# Sheet1.net
KiCad netlist of a schematic drawn in Altium Designer
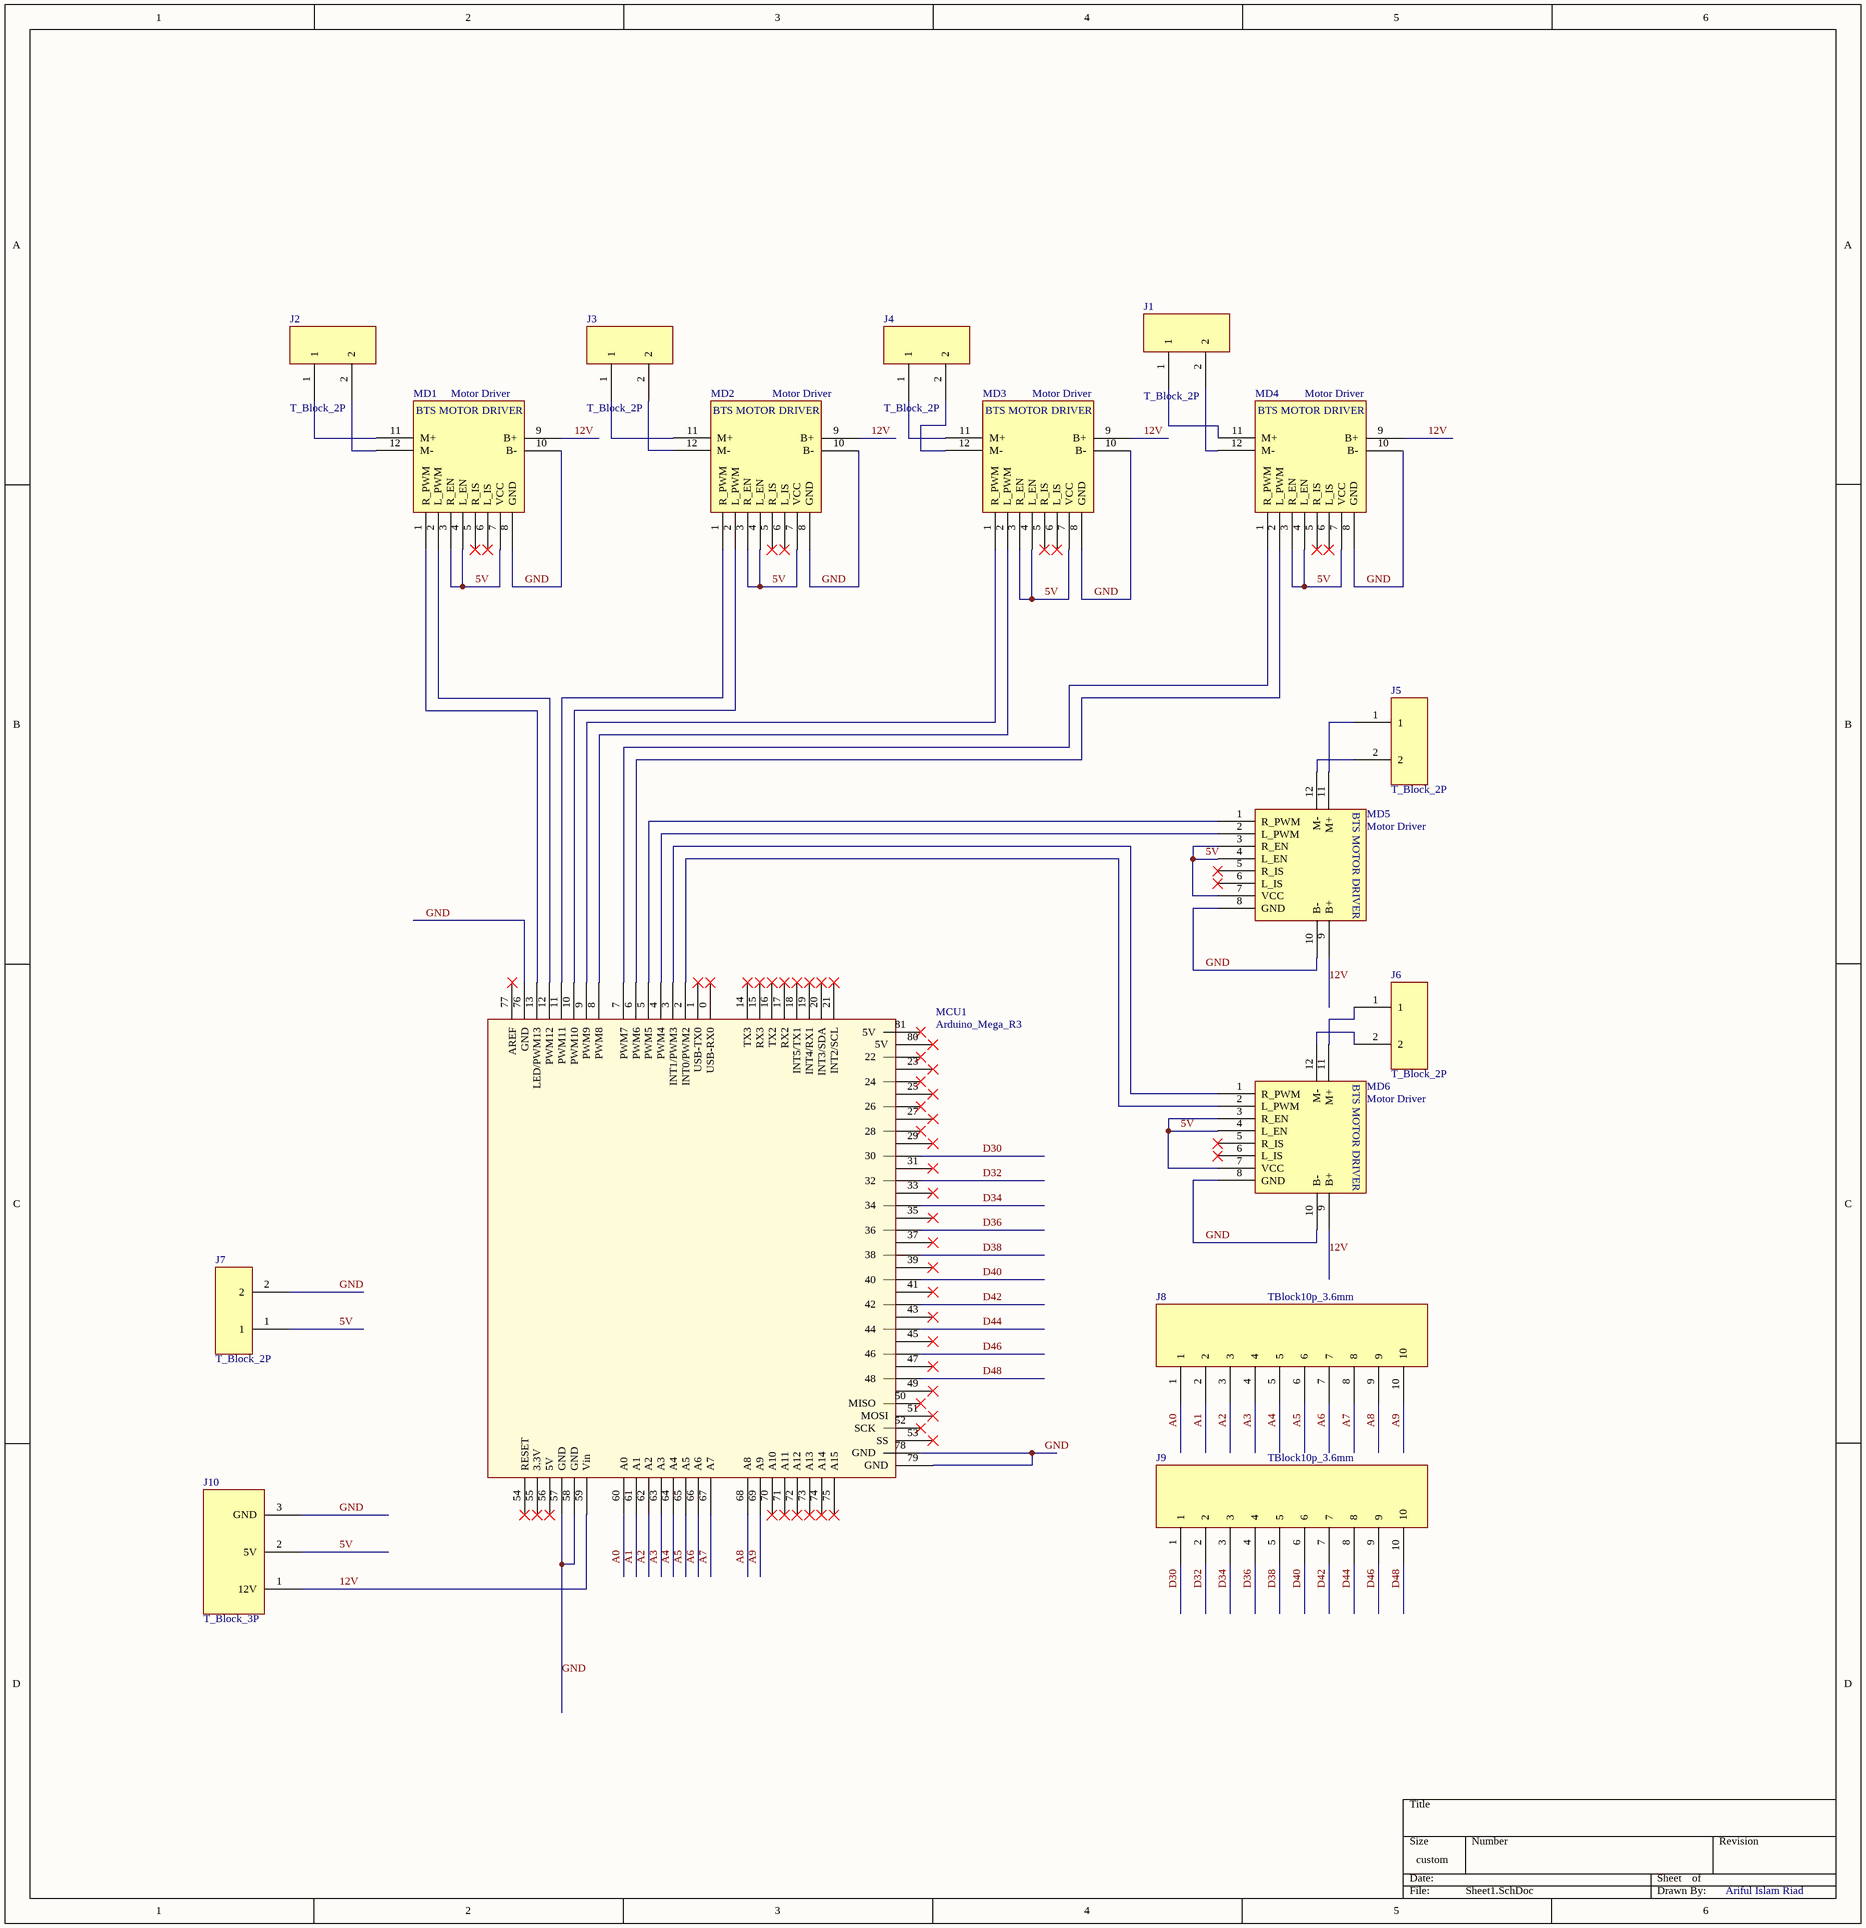
[diagram p0: Sheet1.SchDoc]

(export (version "E")
  (design (tool "Eeschema 10.0.6"))
  (components
    (comp (ref "J1")
      (value "T_Block_2P")
      (footprint "T_Block_2P")
      (description "Terminal")
      (libsource (lib "Schlib1") (part "T_Block_2P"))
    )
    (comp (ref "J2")
      (value "T_Block_2P")
      (footprint "T_Block_2P")
      (description "Terminal")
      (libsource (lib "Schlib1") (part "T_Block_2P"))
    )
    (comp (ref "J3")
      (value "T_Block_2P")
      (footprint "T_Block_2P")
      (description "Terminal")
      (libsource (lib "Schlib1") (part "T_Block_2P"))
    )
    (comp (ref "J4")
      (value "T_Block_2P")
      (footprint "T_Block_2P")
      (description "Terminal")
      (libsource (lib "Schlib1") (part "T_Block_2P"))
    )
    (comp (ref "J5")
      (value "T_Block_2P")
      (footprint "T_Block_2P")
      (description "Terminal")
      (libsource (lib "") (part "T_Block_2P_1"))
    )
    (comp (ref "J6")
      (value "T_Block_2P")
      (footprint "T_Block_2P")
      (description "Terminal")
      (libsource (lib "") (part "T_Block_2P_1"))
    )
    (comp (ref "J7")
      (value "T_Block_2P")
      (footprint "T_Block_2P")
      (description "Terminal")
      (libsource (lib "") (part "T_Block_2P_2"))
    )
    (comp (ref "J8")
      (value "TBlock10p_3.6mm")
      (footprint "T_block_3.6mm")
      (description "Terminal")
      (libsource (lib "Schlib1") (part "TBlock10p_3.6mm"))
    )
    (comp (ref "J9")
      (value "TBlock10p_3.6mm")
      (footprint "T_block_3.6mm")
      (description "Terminal")
      (libsource (lib "Schlib1") (part "TBlock10p_3.6mm"))
    )
    (comp (ref "J10")
      (value "T_Block_3P")
      (footprint "T_Block_3P")
      (description "Terminal")
      (libsource (lib "Schlib1") (part "T_Block_3P"))
    )
    (comp (ref "MCU1")
      (value "Arduino_Mega_R3")
      (footprint "PCB_footprint_mega")
      (description "Arduino Mega")
      (libsource (lib "Schlib1") (part "Mega"))
    )
    (comp (ref "MD1") (value "Motor Driver") (footprint "PCB_BTS") (libsource (lib "Schlib1") (part "BTS")))
    (comp (ref "MD2") (value "Motor Driver") (footprint "PCB_BTS") (libsource (lib "Schlib1") (part "BTS")))
    (comp (ref "MD3") (value "Motor Driver") (footprint "PCB_BTS") (libsource (lib "Schlib1") (part "BTS")))
    (comp (ref "MD4") (value "Motor Driver") (footprint "PCB_BTS") (libsource (lib "Schlib1") (part "BTS")))
    (comp (ref "MD5") (value "Motor Driver") (footprint "PCB_BTS") (libsource (lib "") (part "BTS_1")))
    (comp (ref "MD6") (value "Motor Driver") (footprint "PCB_BTS") (libsource (lib "") (part "BTS_1")))
  )
  (nets
    (net (code "1") (name "/5V") (class "Default")
      (node (ref "J10") (pin "2") (pinfunction "5V_2") (pintype "passive"))
      (node (ref "J7") (pin "1") (pinfunction "1_1") (pintype "passive"))
      (node (ref "MD1") (pin "3") (pinfunction "R_EN_3") (pintype "passive"))
      (node (ref "MD1") (pin "4") (pinfunction "L_EN_4") (pintype "passive"))
      (node (ref "MD1") (pin "7") (pinfunction "VCC_7") (pintype "passive"))
      (node (ref "MD2") (pin "3") (pinfunction "R_EN_3") (pintype "passive"))
      (node (ref "MD2") (pin "4") (pinfunction "L_EN_4") (pintype "passive"))
      (node (ref "MD2") (pin "7") (pinfunction "VCC_7") (pintype "passive"))
      (node (ref "MD3") (pin "3") (pinfunction "R_EN_3") (pintype "passive"))
      (node (ref "MD3") (pin "4") (pinfunction "L_EN_4") (pintype "passive"))
      (node (ref "MD3") (pin "7") (pinfunction "VCC_7") (pintype "passive"))
      (node (ref "MD4") (pin "3") (pinfunction "R_EN_3") (pintype "passive"))
      (node (ref "MD4") (pin "4") (pinfunction "L_EN_4") (pintype "passive"))
      (node (ref "MD4") (pin "7") (pinfunction "VCC_7") (pintype "passive"))
      (node (ref "MD5") (pin "3") (pinfunction "R_EN_3") (pintype "passive"))
      (node (ref "MD5") (pin "4") (pinfunction "L_EN_4") (pintype "passive"))
      (node (ref "MD5") (pin "7") (pinfunction "VCC_7") (pintype "passive"))
      (node (ref "MD6") (pin "3") (pinfunction "R_EN_3") (pintype "passive"))
      (node (ref "MD6") (pin "4") (pinfunction "L_EN_4") (pintype "passive"))
      (node (ref "MD6") (pin "7") (pinfunction "VCC_7") (pintype "passive"))
    )
    (net (code "2") (name "/12V") (class "Default")
      (node (ref "J10") (pin "1") (pinfunction "12V_1") (pintype "passive"))
      (node (ref "MCU1") (pin "59") (pinfunction "Vin_59") (pintype "passive"))
      (node (ref "MD1") (pin "9") (pinfunction "B+_9") (pintype "passive"))
      (node (ref "MD2") (pin "9") (pinfunction "B+_9") (pintype "passive"))
      (node (ref "MD3") (pin "9") (pinfunction "B+_9") (pintype "passive"))
      (node (ref "MD4") (pin "9") (pinfunction "B+_9") (pintype "passive"))
      (node (ref "MD5") (pin "9") (pinfunction "B+_9") (pintype "passive"))
      (node (ref "MD6") (pin "9") (pinfunction "B+_9") (pintype "passive"))
    )
    (net (code "3") (name "/A0") (class "Default")
      (node (ref "J8") (pin "1") (pinfunction "1_1") (pintype "passive"))
      (node (ref "MCU1") (pin "60") (pinfunction "A0_60") (pintype "passive"))
    )
    (net (code "4") (name "/A1") (class "Default")
      (node (ref "J8") (pin "2") (pinfunction "2_2") (pintype "passive"))
      (node (ref "MCU1") (pin "61") (pinfunction "A1_61") (pintype "passive"))
    )
    (net (code "5") (name "/A2") (class "Default")
      (node (ref "J8") (pin "3") (pinfunction "3_3") (pintype "passive"))
      (node (ref "MCU1") (pin "62") (pinfunction "A2_62") (pintype "passive"))
    )
    (net (code "6") (name "/A3") (class "Default")
      (node (ref "J8") (pin "4") (pinfunction "4_4") (pintype "passive"))
      (node (ref "MCU1") (pin "63") (pinfunction "A3_63") (pintype "passive"))
    )
    (net (code "7") (name "/A4") (class "Default")
      (node (ref "J8") (pin "5") (pinfunction "5_5") (pintype "passive"))
      (node (ref "MCU1") (pin "64") (pinfunction "A4_64") (pintype "passive"))
    )
    (net (code "8") (name "/A5") (class "Default")
      (node (ref "J8") (pin "6") (pinfunction "6_6") (pintype "passive"))
      (node (ref "MCU1") (pin "65") (pinfunction "A5_65") (pintype "passive"))
    )
    (net (code "9") (name "/A6") (class "Default")
      (node (ref "J8") (pin "7") (pinfunction "7_7") (pintype "passive"))
      (node (ref "MCU1") (pin "66") (pinfunction "A6_66") (pintype "passive"))
    )
    (net (code "10") (name "/A7") (class "Default")
      (node (ref "J8") (pin "8") (pinfunction "8_8") (pintype "passive"))
      (node (ref "MCU1") (pin "67") (pinfunction "A7_67") (pintype "passive"))
    )
    (net (code "11") (name "/A8") (class "Default")
      (node (ref "J8") (pin "9") (pinfunction "9_9") (pintype "passive"))
      (node (ref "MCU1") (pin "68") (pinfunction "A8_68") (pintype "passive"))
    )
    (net (code "12") (name "/A9") (class "Default")
      (node (ref "J8") (pin "10") (pinfunction "10_10") (pintype "passive"))
      (node (ref "MCU1") (pin "69") (pinfunction "A9_69") (pintype "passive"))
    )
    (net (code "13") (name "/D30") (class "Default")
      (node (ref "J9") (pin "1") (pinfunction "1_1") (pintype "passive"))
      (node (ref "MCU1") (pin "30") (pinfunction "30_30") (pintype "passive"))
    )
    (net (code "14") (name "/D32") (class "Default")
      (node (ref "J9") (pin "2") (pinfunction "2_2") (pintype "passive"))
      (node (ref "MCU1") (pin "32") (pinfunction "32_32") (pintype "passive"))
    )
    (net (code "15") (name "/D34") (class "Default")
      (node (ref "J9") (pin "3") (pinfunction "3_3") (pintype "passive"))
      (node (ref "MCU1") (pin "34") (pinfunction "34_34") (pintype "passive"))
    )
    (net (code "16") (name "/D36") (class "Default")
      (node (ref "J9") (pin "4") (pinfunction "4_4") (pintype "passive"))
      (node (ref "MCU1") (pin "36") (pinfunction "36_36") (pintype "passive"))
    )
    (net (code "17") (name "/D38") (class "Default")
      (node (ref "J9") (pin "5") (pinfunction "5_5") (pintype "passive"))
      (node (ref "MCU1") (pin "38") (pinfunction "38_38") (pintype "passive"))
    )
    (net (code "18") (name "/D40") (class "Default")
      (node (ref "J9") (pin "6") (pinfunction "6_6") (pintype "passive"))
      (node (ref "MCU1") (pin "40") (pinfunction "40_40") (pintype "passive"))
    )
    (net (code "19") (name "/D42") (class "Default")
      (node (ref "J9") (pin "7") (pinfunction "7_7") (pintype "passive"))
      (node (ref "MCU1") (pin "42") (pinfunction "42_42") (pintype "passive"))
    )
    (net (code "20") (name "/D44") (class "Default")
      (node (ref "J9") (pin "8") (pinfunction "8_8") (pintype "passive"))
      (node (ref "MCU1") (pin "44") (pinfunction "44_44") (pintype "passive"))
    )
    (net (code "21") (name "/D46") (class "Default")
      (node (ref "J9") (pin "9") (pinfunction "9_9") (pintype "passive"))
      (node (ref "MCU1") (pin "46") (pinfunction "46_46") (pintype "passive"))
    )
    (net (code "22") (name "/D48") (class "Default")
      (node (ref "J9") (pin "10") (pinfunction "10_10") (pintype "passive"))
      (node (ref "MCU1") (pin "48") (pinfunction "48_48") (pintype "passive"))
    )
    (net (code "23") (name "/GND") (class "Default")
      (node (ref "J10") (pin "3") (pinfunction "GND_3") (pintype "passive"))
      (node (ref "J7") (pin "2") (pinfunction "2_2") (pintype "passive"))
      (node (ref "MCU1") (pin "57") (pinfunction "GND_57") (pintype "passive"))
      (node (ref "MCU1") (pin "58") (pinfunction "GND_58") (pintype "passive"))
      (node (ref "MCU1") (pin "76") (pinfunction "GND_76") (pintype "passive"))
      (node (ref "MCU1") (pin "78") (pinfunction "GND_78") (pintype "passive"))
      (node (ref "MCU1") (pin "79") (pinfunction "GND_79") (pintype "passive"))
      (node (ref "MD1") (pin "10") (pinfunction "B-_10") (pintype "passive"))
      (node (ref "MD1") (pin "8") (pinfunction "GND_8") (pintype "passive"))
      (node (ref "MD2") (pin "10") (pinfunction "B-_10") (pintype "passive"))
      (node (ref "MD2") (pin "8") (pinfunction "GND_8") (pintype "passive"))
      (node (ref "MD3") (pin "10") (pinfunction "B-_10") (pintype "passive"))
      (node (ref "MD3") (pin "8") (pinfunction "GND_8") (pintype "passive"))
      (node (ref "MD4") (pin "10") (pinfunction "B-_10") (pintype "passive"))
      (node (ref "MD4") (pin "8") (pinfunction "GND_8") (pintype "passive"))
      (node (ref "MD5") (pin "10") (pinfunction "B-_10") (pintype "passive"))
      (node (ref "MD5") (pin "8") (pinfunction "GND_8") (pintype "passive"))
      (node (ref "MD6") (pin "10") (pinfunction "B-_10") (pintype "passive"))
      (node (ref "MD6") (pin "8") (pinfunction "GND_8") (pintype "passive"))
    )
    (net (code "24") (name "Net-(MCU1-INT0{slash}PWM2)") (class "Default")
      (node (ref "MCU1") (pin "2") (pinfunction "INT0/PWM2_2") (pintype "passive"))
      (node (ref "MD6") (pin "2") (pinfunction "L_PWM_2") (pintype "passive"))
    )
    (net (code "25") (name "Net-(MCU1-INT1{slash}PWM3)") (class "Default")
      (node (ref "MCU1") (pin "3") (pinfunction "INT1/PWM3_3") (pintype "passive"))
      (node (ref "MD6") (pin "1") (pinfunction "R_PWM_1") (pintype "passive"))
    )
    (net (code "26") (name "Net-(MCU1-LED{slash}PWM13)") (class "Default")
      (node (ref "MCU1") (pin "13") (pinfunction "LED/PWM13_13") (pintype "passive"))
      (node (ref "MD1") (pin "1") (pinfunction "R_PWM_1") (pintype "passive"))
    )
    (net (code "27") (name "Net-(MCU1-PWM4)") (class "Default")
      (node (ref "MCU1") (pin "4") (pinfunction "PWM4_4") (pintype "passive"))
      (node (ref "MD5") (pin "2") (pinfunction "L_PWM_2") (pintype "passive"))
    )
    (net (code "28") (name "Net-(MCU1-PWM5)") (class "Default")
      (node (ref "MCU1") (pin "5") (pinfunction "PWM5_5") (pintype "passive"))
      (node (ref "MD5") (pin "1") (pinfunction "R_PWM_1") (pintype "passive"))
    )
    (net (code "29") (name "Net-(MCU1-PWM6)") (class "Default")
      (node (ref "MCU1") (pin "6") (pinfunction "PWM6_6") (pintype "passive"))
      (node (ref "MD4") (pin "2") (pinfunction "L_PWM_2") (pintype "passive"))
    )
    (net (code "30") (name "Net-(MCU1-PWM7)") (class "Default")
      (node (ref "MCU1") (pin "7") (pinfunction "PWM7_7") (pintype "passive"))
      (node (ref "MD4") (pin "1") (pinfunction "R_PWM_1") (pintype "passive"))
    )
    (net (code "31") (name "Net-(MCU1-PWM8)") (class "Default")
      (node (ref "MCU1") (pin "8") (pinfunction "PWM8_8") (pintype "passive"))
      (node (ref "MD3") (pin "2") (pinfunction "L_PWM_2") (pintype "passive"))
    )
    (net (code "32") (name "Net-(MCU1-PWM9)") (class "Default")
      (node (ref "MCU1") (pin "9") (pinfunction "PWM9_9") (pintype "passive"))
      (node (ref "MD3") (pin "1") (pinfunction "R_PWM_1") (pintype "passive"))
    )
    (net (code "33") (name "Net-(MCU1-PWM10)") (class "Default")
      (node (ref "MCU1") (pin "10") (pinfunction "PWM10_10") (pintype "passive"))
      (node (ref "MD2") (pin "2") (pinfunction "L_PWM_2") (pintype "passive"))
    )
    (net (code "34") (name "Net-(MCU1-PWM11)") (class "Default")
      (node (ref "MCU1") (pin "11") (pinfunction "PWM11_11") (pintype "passive"))
      (node (ref "MD2") (pin "1") (pinfunction "R_PWM_1") (pintype "passive"))
    )
    (net (code "35") (name "Net-(MCU1-PWM12)") (class "Default")
      (node (ref "MCU1") (pin "12") (pinfunction "PWM12_12") (pintype "passive"))
      (node (ref "MD1") (pin "2") (pinfunction "L_PWM_2") (pintype "passive"))
    )
    (net (code "36") (name "Net-(MD1-M+)") (class "Default")
      (node (ref "J2") (pin "1") (pinfunction "1_1") (pintype "passive"))
      (node (ref "MD1") (pin "11") (pinfunction "M+_11") (pintype "passive"))
    )
    (net (code "37") (name "Net-(MD1-M-)") (class "Default")
      (node (ref "J2") (pin "2") (pinfunction "2_2") (pintype "passive"))
      (node (ref "MD1") (pin "12") (pinfunction "M-_12") (pintype "passive"))
    )
    (net (code "38") (name "Net-(MD2-M+)") (class "Default")
      (node (ref "J3") (pin "1") (pinfunction "1_1") (pintype "passive"))
      (node (ref "MD2") (pin "11") (pinfunction "M+_11") (pintype "passive"))
    )
    (net (code "39") (name "Net-(MD2-M-)") (class "Default")
      (node (ref "J3") (pin "2") (pinfunction "2_2") (pintype "passive"))
      (node (ref "MD2") (pin "12") (pinfunction "M-_12") (pintype "passive"))
    )
    (net (code "40") (name "Net-(MD3-M+)") (class "Default")
      (node (ref "J4") (pin "1") (pinfunction "1_1") (pintype "passive"))
      (node (ref "MD3") (pin "11") (pinfunction "M+_11") (pintype "passive"))
    )
    (net (code "41") (name "Net-(MD3-M-)") (class "Default")
      (node (ref "J4") (pin "2") (pinfunction "2_2") (pintype "passive"))
      (node (ref "MD3") (pin "12") (pinfunction "M-_12") (pintype "passive"))
    )
    (net (code "42") (name "Net-(MD4-M+)") (class "Default")
      (node (ref "J1") (pin "1") (pinfunction "1_1") (pintype "passive"))
      (node (ref "MD4") (pin "11") (pinfunction "M+_11") (pintype "passive"))
    )
    (net (code "43") (name "Net-(MD4-M-)") (class "Default")
      (node (ref "J1") (pin "2") (pinfunction "2_2") (pintype "passive"))
      (node (ref "MD4") (pin "12") (pinfunction "M-_12") (pintype "passive"))
    )
    (net (code "44") (name "Net-(MD5-M+)") (class "Default")
      (node (ref "J5") (pin "1") (pinfunction "1_1") (pintype "passive"))
      (node (ref "MD5") (pin "11") (pinfunction "M+_11") (pintype "passive"))
    )
    (net (code "45") (name "Net-(MD5-M-)") (class "Default")
      (node (ref "J5") (pin "2") (pinfunction "2_2") (pintype "passive"))
      (node (ref "MD5") (pin "12") (pinfunction "M-_12") (pintype "passive"))
    )
    (net (code "46") (name "Net-(MD6-M+)") (class "Default")
      (node (ref "J6") (pin "1") (pinfunction "1_1") (pintype "passive"))
      (node (ref "MD6") (pin "11") (pinfunction "M+_11") (pintype "passive"))
    )
    (net (code "47") (name "Net-(MD6-M-)") (class "Default")
      (node (ref "J6") (pin "2") (pinfunction "2_2") (pintype "passive"))
      (node (ref "MD6") (pin "12") (pinfunction "M-_12") (pintype "passive"))
    )
    (net (code "48") (name "unconnected-(MCU1-3.3V-Pad55)") (class "Default")
      (node (ref "MCU1") (pin "55") (pinfunction "3.3V_55") (pintype "passive+no_connect"))
    )
    (net (code "49") (name "unconnected-(MCU1-5V-Pad56)") (class "Default")
      (node (ref "MCU1") (pin "56") (pinfunction "5V_56") (pintype "passive+no_connect"))
    )
    (net (code "50") (name "unconnected-(MCU1-5V-Pad80)") (class "Default")
      (node (ref "MCU1") (pin "80") (pinfunction "5V_80") (pintype "passive+no_connect"))
    )
    (net (code "51") (name "unconnected-(MCU1-5V-Pad81)") (class "Default")
      (node (ref "MCU1") (pin "81") (pinfunction "5V_81") (pintype "passive+no_connect"))
    )
    (net (code "52") (name "unconnected-(MCU1-A10-Pad70)") (class "Default")
      (node (ref "MCU1") (pin "70") (pinfunction "A10_70") (pintype "passive+no_connect"))
    )
    (net (code "53") (name "unconnected-(MCU1-A11-Pad71)") (class "Default")
      (node (ref "MCU1") (pin "71") (pinfunction "A11_71") (pintype "passive+no_connect"))
    )
    (net (code "54") (name "unconnected-(MCU1-A12-Pad72)") (class "Default")
      (node (ref "MCU1") (pin "72") (pinfunction "A12_72") (pintype "passive+no_connect"))
    )
    (net (code "55") (name "unconnected-(MCU1-A13-Pad73)") (class "Default")
      (node (ref "MCU1") (pin "73") (pinfunction "A13_73") (pintype "passive+no_connect"))
    )
    (net (code "56") (name "unconnected-(MCU1-A14-Pad74)") (class "Default")
      (node (ref "MCU1") (pin "74") (pinfunction "A14_74") (pintype "passive+no_connect"))
    )
    (net (code "57") (name "unconnected-(MCU1-A15-Pad75)") (class "Default")
      (node (ref "MCU1") (pin "75") (pinfunction "A15_75") (pintype "passive+no_connect"))
    )
    (net (code "58") (name "unconnected-(MCU1-AREF-Pad77)") (class "Default")
      (node (ref "MCU1") (pin "77") (pinfunction "AREF_77") (pintype "passive+no_connect"))
    )
    (net (code "59") (name "unconnected-(MCU1-INT2{slash}SCL-Pad21)") (class "Default")
      (node (ref "MCU1") (pin "21") (pinfunction "INT2/SCL_21") (pintype "passive+no_connect"))
    )
    (net (code "60") (name "unconnected-(MCU1-INT3{slash}SDA-Pad20)") (class "Default")
      (node (ref "MCU1") (pin "20") (pinfunction "INT3/SDA_20") (pintype "passive+no_connect"))
    )
    (net (code "61") (name "unconnected-(MCU1-INT4{slash}RX1-Pad19)") (class "Default")
      (node (ref "MCU1") (pin "19") (pinfunction "INT4/RX1_19") (pintype "passive+no_connect"))
    )
    (net (code "62") (name "unconnected-(MCU1-INT5{slash}TX1-Pad18)") (class "Default")
      (node (ref "MCU1") (pin "18") (pinfunction "INT5/TX1_18") (pintype "passive+no_connect"))
    )
    (net (code "63") (name "unconnected-(MCU1-MISO-Pad50)") (class "Default")
      (node (ref "MCU1") (pin "50") (pinfunction "MISO_50") (pintype "passive+no_connect"))
    )
    (net (code "64") (name "unconnected-(MCU1-MOSI-Pad51)") (class "Default")
      (node (ref "MCU1") (pin "51") (pinfunction "MOSI_51") (pintype "passive+no_connect"))
    )
    (net (code "65") (name "unconnected-(MCU1-Pad22)") (class "Default")
      (node (ref "MCU1") (pin "22") (pinfunction "22_22") (pintype "passive+no_connect"))
    )
    (net (code "66") (name "unconnected-(MCU1-Pad23)") (class "Default")
      (node (ref "MCU1") (pin "23") (pinfunction "23_23") (pintype "passive+no_connect"))
    )
    (net (code "67") (name "unconnected-(MCU1-Pad24)") (class "Default")
      (node (ref "MCU1") (pin "24") (pinfunction "24_24") (pintype "passive+no_connect"))
    )
    (net (code "68") (name "unconnected-(MCU1-Pad25)") (class "Default")
      (node (ref "MCU1") (pin "25") (pinfunction "25_25") (pintype "passive+no_connect"))
    )
    (net (code "69") (name "unconnected-(MCU1-Pad26)") (class "Default")
      (node (ref "MCU1") (pin "26") (pinfunction "26_26") (pintype "passive+no_connect"))
    )
    (net (code "70") (name "unconnected-(MCU1-Pad27)") (class "Default")
      (node (ref "MCU1") (pin "27") (pinfunction "27_27") (pintype "passive+no_connect"))
    )
    (net (code "71") (name "unconnected-(MCU1-Pad28)") (class "Default")
      (node (ref "MCU1") (pin "28") (pinfunction "28_28") (pintype "passive+no_connect"))
    )
    (net (code "72") (name "unconnected-(MCU1-Pad29)") (class "Default")
      (node (ref "MCU1") (pin "29") (pinfunction "29_29") (pintype "passive+no_connect"))
    )
    (net (code "73") (name "unconnected-(MCU1-Pad31)") (class "Default")
      (node (ref "MCU1") (pin "31") (pinfunction "31_31") (pintype "passive+no_connect"))
    )
    (net (code "74") (name "unconnected-(MCU1-Pad33)") (class "Default")
      (node (ref "MCU1") (pin "33") (pinfunction "33_33") (pintype "passive+no_connect"))
    )
    (net (code "75") (name "unconnected-(MCU1-Pad35)") (class "Default")
      (node (ref "MCU1") (pin "35") (pinfunction "35_35") (pintype "passive+no_connect"))
    )
    (net (code "76") (name "unconnected-(MCU1-Pad37)") (class "Default")
      (node (ref "MCU1") (pin "37") (pinfunction "37_37") (pintype "passive+no_connect"))
    )
    (net (code "77") (name "unconnected-(MCU1-Pad39)") (class "Default")
      (node (ref "MCU1") (pin "39") (pinfunction "39_39") (pintype "passive+no_connect"))
    )
    (net (code "78") (name "unconnected-(MCU1-Pad41)") (class "Default")
      (node (ref "MCU1") (pin "41") (pinfunction "41_41") (pintype "passive+no_connect"))
    )
    (net (code "79") (name "unconnected-(MCU1-Pad43)") (class "Default")
      (node (ref "MCU1") (pin "43") (pinfunction "43_43") (pintype "passive+no_connect"))
    )
    (net (code "80") (name "unconnected-(MCU1-Pad45)") (class "Default")
      (node (ref "MCU1") (pin "45") (pinfunction "45_45") (pintype "passive+no_connect"))
    )
    (net (code "81") (name "unconnected-(MCU1-Pad47)") (class "Default")
      (node (ref "MCU1") (pin "47") (pinfunction "47_47") (pintype "passive+no_connect"))
    )
    (net (code "82") (name "unconnected-(MCU1-Pad49)") (class "Default")
      (node (ref "MCU1") (pin "49") (pinfunction "49_49") (pintype "passive+no_connect"))
    )
    (net (code "83") (name "unconnected-(MCU1-RESET-Pad54)") (class "Default")
      (node (ref "MCU1") (pin "54") (pinfunction "RESET_54") (pintype "passive+no_connect"))
    )
    (net (code "84") (name "unconnected-(MCU1-RX2-Pad17)") (class "Default")
      (node (ref "MCU1") (pin "17") (pinfunction "RX2_17") (pintype "passive+no_connect"))
    )
    (net (code "85") (name "unconnected-(MCU1-RX3-Pad15)") (class "Default")
      (node (ref "MCU1") (pin "15") (pinfunction "RX3_15") (pintype "passive+no_connect"))
    )
    (net (code "86") (name "unconnected-(MCU1-SCK-Pad52)") (class "Default")
      (node (ref "MCU1") (pin "52") (pinfunction "SCK_52") (pintype "passive+no_connect"))
    )
    (net (code "87") (name "unconnected-(MCU1-SS-Pad53)") (class "Default")
      (node (ref "MCU1") (pin "53") (pinfunction "SS_53") (pintype "passive+no_connect"))
    )
    (net (code "88") (name "unconnected-(MCU1-TX2-Pad16)") (class "Default")
      (node (ref "MCU1") (pin "16") (pinfunction "TX2_16") (pintype "passive+no_connect"))
    )
    (net (code "89") (name "unconnected-(MCU1-TX3-Pad14)") (class "Default")
      (node (ref "MCU1") (pin "14") (pinfunction "TX3_14") (pintype "passive+no_connect"))
    )
    (net (code "90") (name "unconnected-(MCU1-USB-RX0-Pad0)") (class "Default")
      (node (ref "MCU1") (pin "0") (pinfunction "USB-RX0_0") (pintype "passive+no_connect"))
    )
    (net (code "91") (name "unconnected-(MCU1-USB-TX0-Pad1)") (class "Default")
      (node (ref "MCU1") (pin "1") (pinfunction "USB-TX0_1") (pintype "passive+no_connect"))
    )
    (net (code "92") (name "unconnected-(MD1-L_IS-Pad6)") (class "Default")
      (node (ref "MD1") (pin "6") (pinfunction "L_IS_6") (pintype "passive+no_connect"))
    )
    (net (code "93") (name "unconnected-(MD1-R_IS-Pad5)") (class "Default")
      (node (ref "MD1") (pin "5") (pinfunction "R_IS_5") (pintype "passive+no_connect"))
    )
    (net (code "94") (name "unconnected-(MD2-L_IS-Pad6)") (class "Default")
      (node (ref "MD2") (pin "6") (pinfunction "L_IS_6") (pintype "passive+no_connect"))
    )
    (net (code "95") (name "unconnected-(MD2-R_IS-Pad5)") (class "Default")
      (node (ref "MD2") (pin "5") (pinfunction "R_IS_5") (pintype "passive+no_connect"))
    )
    (net (code "96") (name "unconnected-(MD3-L_IS-Pad6)") (class "Default")
      (node (ref "MD3") (pin "6") (pinfunction "L_IS_6") (pintype "passive+no_connect"))
    )
    (net (code "97") (name "unconnected-(MD3-R_IS-Pad5)") (class "Default")
      (node (ref "MD3") (pin "5") (pinfunction "R_IS_5") (pintype "passive+no_connect"))
    )
    (net (code "98") (name "unconnected-(MD4-L_IS-Pad6)") (class "Default")
      (node (ref "MD4") (pin "6") (pinfunction "L_IS_6") (pintype "passive+no_connect"))
    )
    (net (code "99") (name "unconnected-(MD4-R_IS-Pad5)") (class "Default")
      (node (ref "MD4") (pin "5") (pinfunction "R_IS_5") (pintype "passive+no_connect"))
    )
    (net (code "100") (name "unconnected-(MD5-L_IS-Pad6)") (class "Default")
      (node (ref "MD5") (pin "6") (pinfunction "L_IS_6") (pintype "passive+no_connect"))
    )
    (net (code "101") (name "unconnected-(MD5-R_IS-Pad5)") (class "Default")
      (node (ref "MD5") (pin "5") (pinfunction "R_IS_5") (pintype "passive+no_connect"))
    )
    (net (code "102") (name "unconnected-(MD6-L_IS-Pad6)") (class "Default")
      (node (ref "MD6") (pin "6") (pinfunction "L_IS_6") (pintype "passive+no_connect"))
    )
    (net (code "103") (name "unconnected-(MD6-R_IS-Pad5)") (class "Default")
      (node (ref "MD6") (pin "5") (pinfunction "R_IS_5") (pintype "passive+no_connect"))
    )
  )
)
